# Buck_schematics.net
KiCad netlist of a schematic drawn in Altium Designer
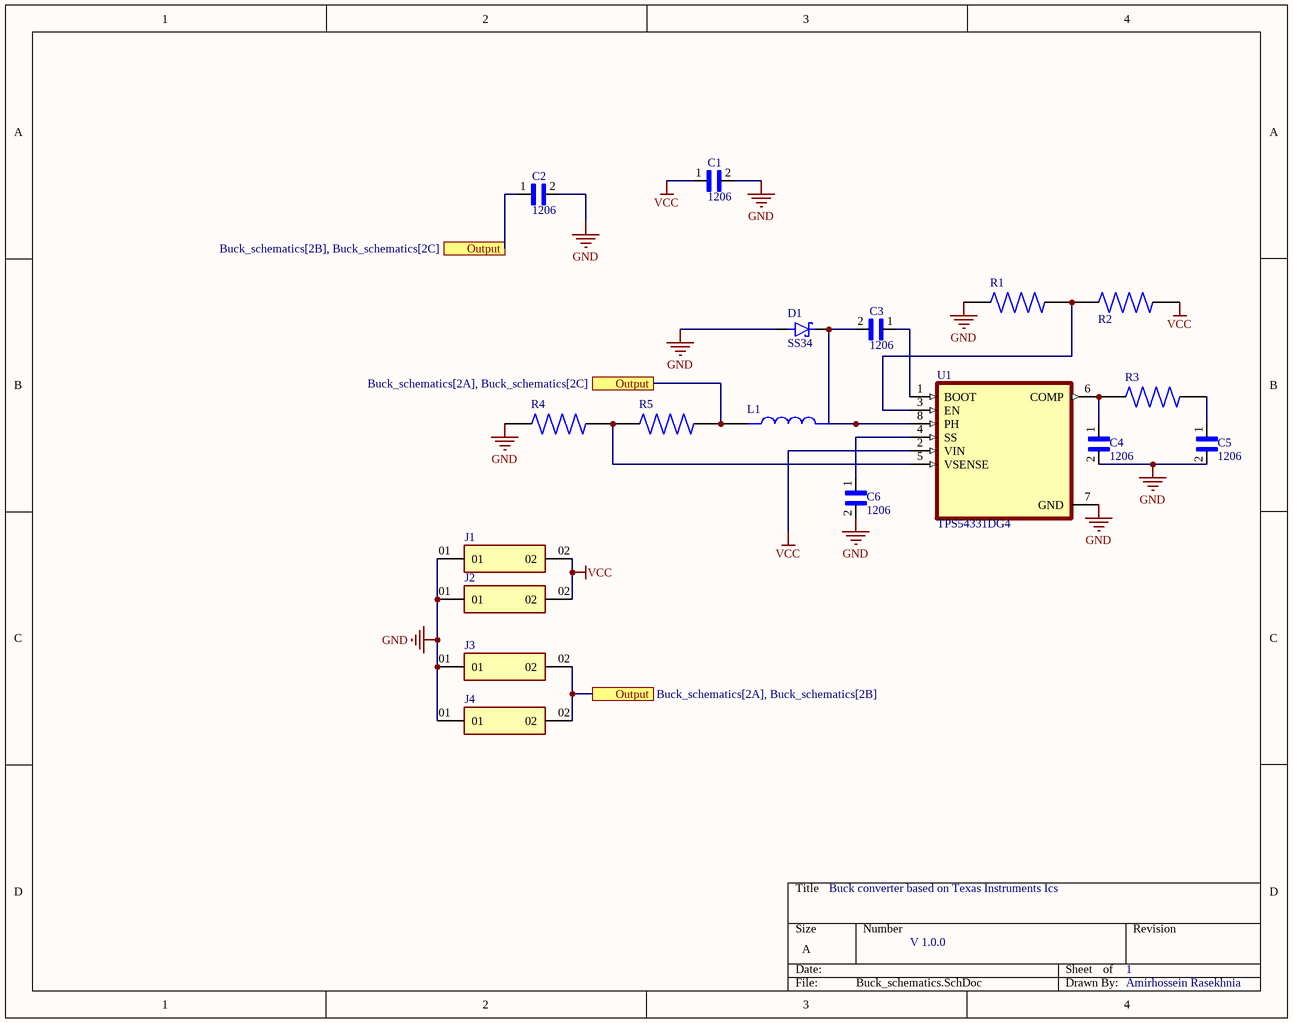
[diagram p0: Buck_schematics.SchDoc]

(export (version "E")
  (design (tool "Eeschema 10.0.6"))
  (components
    (comp (ref "C1")
      (value "1206")
      (footprint "CAPC3216X170N")
      (fields (field (name "MP") "VJ1206A270KXCAP"))
      (libsource (lib "VJ1206A270KXCAP") (part "VJ1206A270KXCAP"))
    )
    (comp (ref "C2")
      (value "1206")
      (footprint "CAPC3216X170N")
      (fields (field (name "MP") "VJ1206A270KXCAP"))
      (libsource (lib "VJ1206A270KXCAP") (part "VJ1206A270KXCAP"))
    )
    (comp (ref "C3")
      (value "1206")
      (footprint "CAPC3216X170N")
      (fields (field (name "MP") "VJ1206A270KXCAP"))
      (libsource (lib "") (part "VJ1206A270KXCAP_2"))
    )
    (comp (ref "C4")
      (value "1206")
      (footprint "CAPC3216X170N")
      (fields (field (name "MP") "VJ1206A270KXCAP"))
      (libsource (lib "") (part "VJ1206A270KXCAP_1"))
    )
    (comp (ref "C5")
      (value "1206")
      (footprint "CAPC3216X170N")
      (fields (field (name "MP") "VJ1206A270KXCAP"))
      (libsource (lib "") (part "VJ1206A270KXCAP_1"))
    )
    (comp (ref "C6")
      (value "1206")
      (footprint "CAPC3216X170N")
      (fields (field (name "MP") "VJ1206A270KXCAP"))
      (libsource (lib "") (part "VJ1206A270KXCAP_1"))
    )
    (comp (ref "D1")
      (value "SS34")
      (footprint "DIO_SS34")
      (description "3A, 40V, Schottky Rectifier")
      (fields (field (name "MF") "Taiwan Semiconductor"))
      (libsource (lib "SS34") (part "SS34"))
    )
    (comp (ref "J1")
      (value "TSW-101-23-S-D-LL")
      (footprint "SAMTEC_TSW-101-23-S-D-LL")
      (libsource (lib "TSW-101-23-S-D-LL") (part "TSW-101-23-S-D-LL"))
    )
    (comp (ref "J2")
      (value "TSW-101-23-S-D-LL")
      (footprint "SAMTEC_TSW-101-23-S-D-LL")
      (libsource (lib "TSW-101-23-S-D-LL") (part "TSW-101-23-S-D-LL"))
    )
    (comp (ref "J3")
      (value "TSW-101-23-S-D-LL")
      (footprint "SAMTEC_TSW-101-23-S-D-LL")
      (libsource (lib "TSW-101-23-S-D-LL") (part "TSW-101-23-S-D-LL"))
    )
    (comp (ref "J4")
      (value "TSW-101-23-S-D-LL")
      (footprint "SAMTEC_TSW-101-23-S-D-LL")
      (libsource (lib "TSW-101-23-S-D-LL") (part "TSW-101-23-S-D-LL"))
    )
    (comp (ref "L1")
      (value "1255AY-100M=P3")
      (footprint "IND_1255AY-100M=P3")
      (description "Inductor with Inductance: 10uH Tol. +/-20%, Package: 2424 _6060_")
      (fields (field (name "MF") "Murata") (field (name "DIGI-KEY_PART_NUMBER") "490-10800-1-ND"))
      (libsource (lib "1255AY-100M_P3") (part "1255AY-100M=P3"))
    )
    (comp (ref "R1")
      (value "ERJU08J274V")
      (footprint "RES_ERJU08J274V")
      (description "1206 anti-sulfurated resistor 1206 Anti-Sulfurated")
      (fields (field (name "MF") "Panasonic") (field (name "MP") "ERJ-U08J274V"))
      (libsource (lib "ERJU08J274V") (part "ERJU08J274V"))
    )
    (comp (ref "R2")
      (value "ERJU08J274V")
      (footprint "RES_ERJU08J274V")
      (description "1206 anti-sulfurated resistor 1206 Anti-Sulfurated")
      (fields (field (name "MF") "Panasonic") (field (name "MP") "ERJ-U08J274V"))
      (libsource (lib "ERJU08J274V") (part "ERJU08J274V"))
    )
    (comp (ref "R3")
      (value "ERJU08J274V")
      (footprint "RES_ERJU08J274V")
      (description "1206 anti-sulfurated resistor 1206 Anti-Sulfurated")
      (fields (field (name "MF") "Panasonic") (field (name "MP") "ERJ-U08J274V"))
      (libsource (lib "ERJU08J274V") (part "ERJU08J274V"))
    )
    (comp (ref "R4")
      (value "ERJU08J274V")
      (footprint "RES_ERJU08J274V")
      (description "1206 anti-sulfurated resistor 1206 Anti-Sulfurated")
      (fields (field (name "MF") "Panasonic") (field (name "MP") "ERJ-U08J274V"))
      (libsource (lib "ERJU08J274V") (part "ERJU08J274V"))
    )
    (comp (ref "R5")
      (value "ERJU08J274V")
      (footprint "RES_ERJU08J274V")
      (description "1206 anti-sulfurated resistor 1206 Anti-Sulfurated")
      (fields (field (name "MF") "Panasonic") (field (name "MP") "ERJ-U08J274V"))
      (libsource (lib "ERJU08J274V") (part "ERJU08J274V"))
    )
    (comp (ref "U1")
      (value "TPS54331DG4")
      (footprint "SOIC127P599X175-8N")
      (description "3.5V to 28V Input, 3A, 570kHz Step-Down Converter with Eco-mode 8-SOIC -40 to 150")
      (fields (field (name "MF") "Texas Instruments"))
      (libsource (lib "TPS54331DG4") (part "TPS54331DG4"))
    )
  )
  (nets
    (net (code "1") (name "/Output") (class "Default")
      (node (ref "C2") (pin "1") (pinfunction "1_1") (pintype "passive"))
      (node (ref "J3") (pin "02") (pinfunction "02_02") (pintype "passive"))
      (node (ref "J4") (pin "02") (pinfunction "02_02") (pintype "passive"))
      (node (ref "L1") (pin "1") (pinfunction "1_1") (pintype "passive"))
      (node (ref "R5") (pin "2") (pinfunction "2_2") (pintype "passive"))
    )
    (net (code "2") (name "GND") (class "Default")
      (node (ref "C1") (pin "2") (pinfunction "2_2") (pintype "passive"))
      (node (ref "C2") (pin "2") (pinfunction "2_2") (pintype "passive"))
      (node (ref "C4") (pin "2") (pinfunction "2_2") (pintype "passive"))
      (node (ref "C5") (pin "2") (pinfunction "2_2") (pintype "passive"))
      (node (ref "C6") (pin "2") (pinfunction "2_2") (pintype "passive"))
      (node (ref "D1") (pin "A") (pinfunction "A_A") (pintype "passive"))
      (node (ref "J1") (pin "01") (pinfunction "01_01") (pintype "passive"))
      (node (ref "J2") (pin "01") (pinfunction "01_01") (pintype "passive"))
      (node (ref "J3") (pin "01") (pinfunction "01_01") (pintype "passive"))
      (node (ref "J4") (pin "01") (pinfunction "01_01") (pintype "passive"))
      (node (ref "R1") (pin "1") (pinfunction "1_1") (pintype "passive"))
      (node (ref "R4") (pin "1") (pinfunction "1_1") (pintype "passive"))
      (node (ref "U1") (pin "7") (pinfunction "GND_7") (pintype "power_in"))
    )
    (net (code "3") (name "Net-(C5-Pad1)") (class "Default")
      (node (ref "C5") (pin "1") (pinfunction "1_1") (pintype "passive"))
      (node (ref "R3") (pin "2") (pinfunction "2_2") (pintype "passive"))
    )
    (net (code "4") (name "Net-(D1-K)") (class "Default")
      (node (ref "C3") (pin "2") (pinfunction "2_2") (pintype "passive"))
      (node (ref "D1") (pin "C") (pinfunction "K_C") (pintype "passive"))
      (node (ref "L1") (pin "2") (pinfunction "2_2") (pintype "passive"))
      (node (ref "U1") (pin "8") (pinfunction "PH_8") (pintype "input"))
    )
    (net (code "5") (name "Net-(U1-BOOT)") (class "Default")
      (node (ref "C3") (pin "1") (pinfunction "1_1") (pintype "passive"))
      (node (ref "U1") (pin "1") (pinfunction "BOOT_1") (pintype "input"))
    )
    (net (code "6") (name "Net-(U1-COMP)") (class "Default")
      (node (ref "C4") (pin "1") (pinfunction "1_1") (pintype "passive"))
      (node (ref "R3") (pin "1") (pinfunction "1_1") (pintype "passive"))
      (node (ref "U1") (pin "6") (pinfunction "COMP_6") (pintype "output"))
    )
    (net (code "7") (name "Net-(U1-EN)") (class "Default")
      (node (ref "R1") (pin "2") (pinfunction "2_2") (pintype "passive"))
      (node (ref "R2") (pin "2") (pinfunction "2_2") (pintype "passive"))
      (node (ref "U1") (pin "3") (pinfunction "EN_3") (pintype "input"))
    )
    (net (code "8") (name "Net-(U1-SS)") (class "Default")
      (node (ref "C6") (pin "1") (pinfunction "1_1") (pintype "passive"))
      (node (ref "U1") (pin "4") (pinfunction "SS_4") (pintype "input"))
    )
    (net (code "9") (name "Net-(U1-VSENSE)") (class "Default")
      (node (ref "R4") (pin "2") (pinfunction "2_2") (pintype "passive"))
      (node (ref "R5") (pin "1") (pinfunction "1_1") (pintype "passive"))
      (node (ref "U1") (pin "5") (pinfunction "VSENSE_5") (pintype "input"))
    )
    (net (code "10") (name "VCC") (class "Default")
      (node (ref "C1") (pin "1") (pinfunction "1_1") (pintype "passive"))
      (node (ref "J1") (pin "02") (pinfunction "02_02") (pintype "passive"))
      (node (ref "J2") (pin "02") (pinfunction "02_02") (pintype "passive"))
      (node (ref "R2") (pin "1") (pinfunction "1_1") (pintype "passive"))
      (node (ref "U1") (pin "2") (pinfunction "VIN_2") (pintype "input"))
    )
  )
)
